# eagle.net
KiCad netlist of a schematic drawn in EAGLE
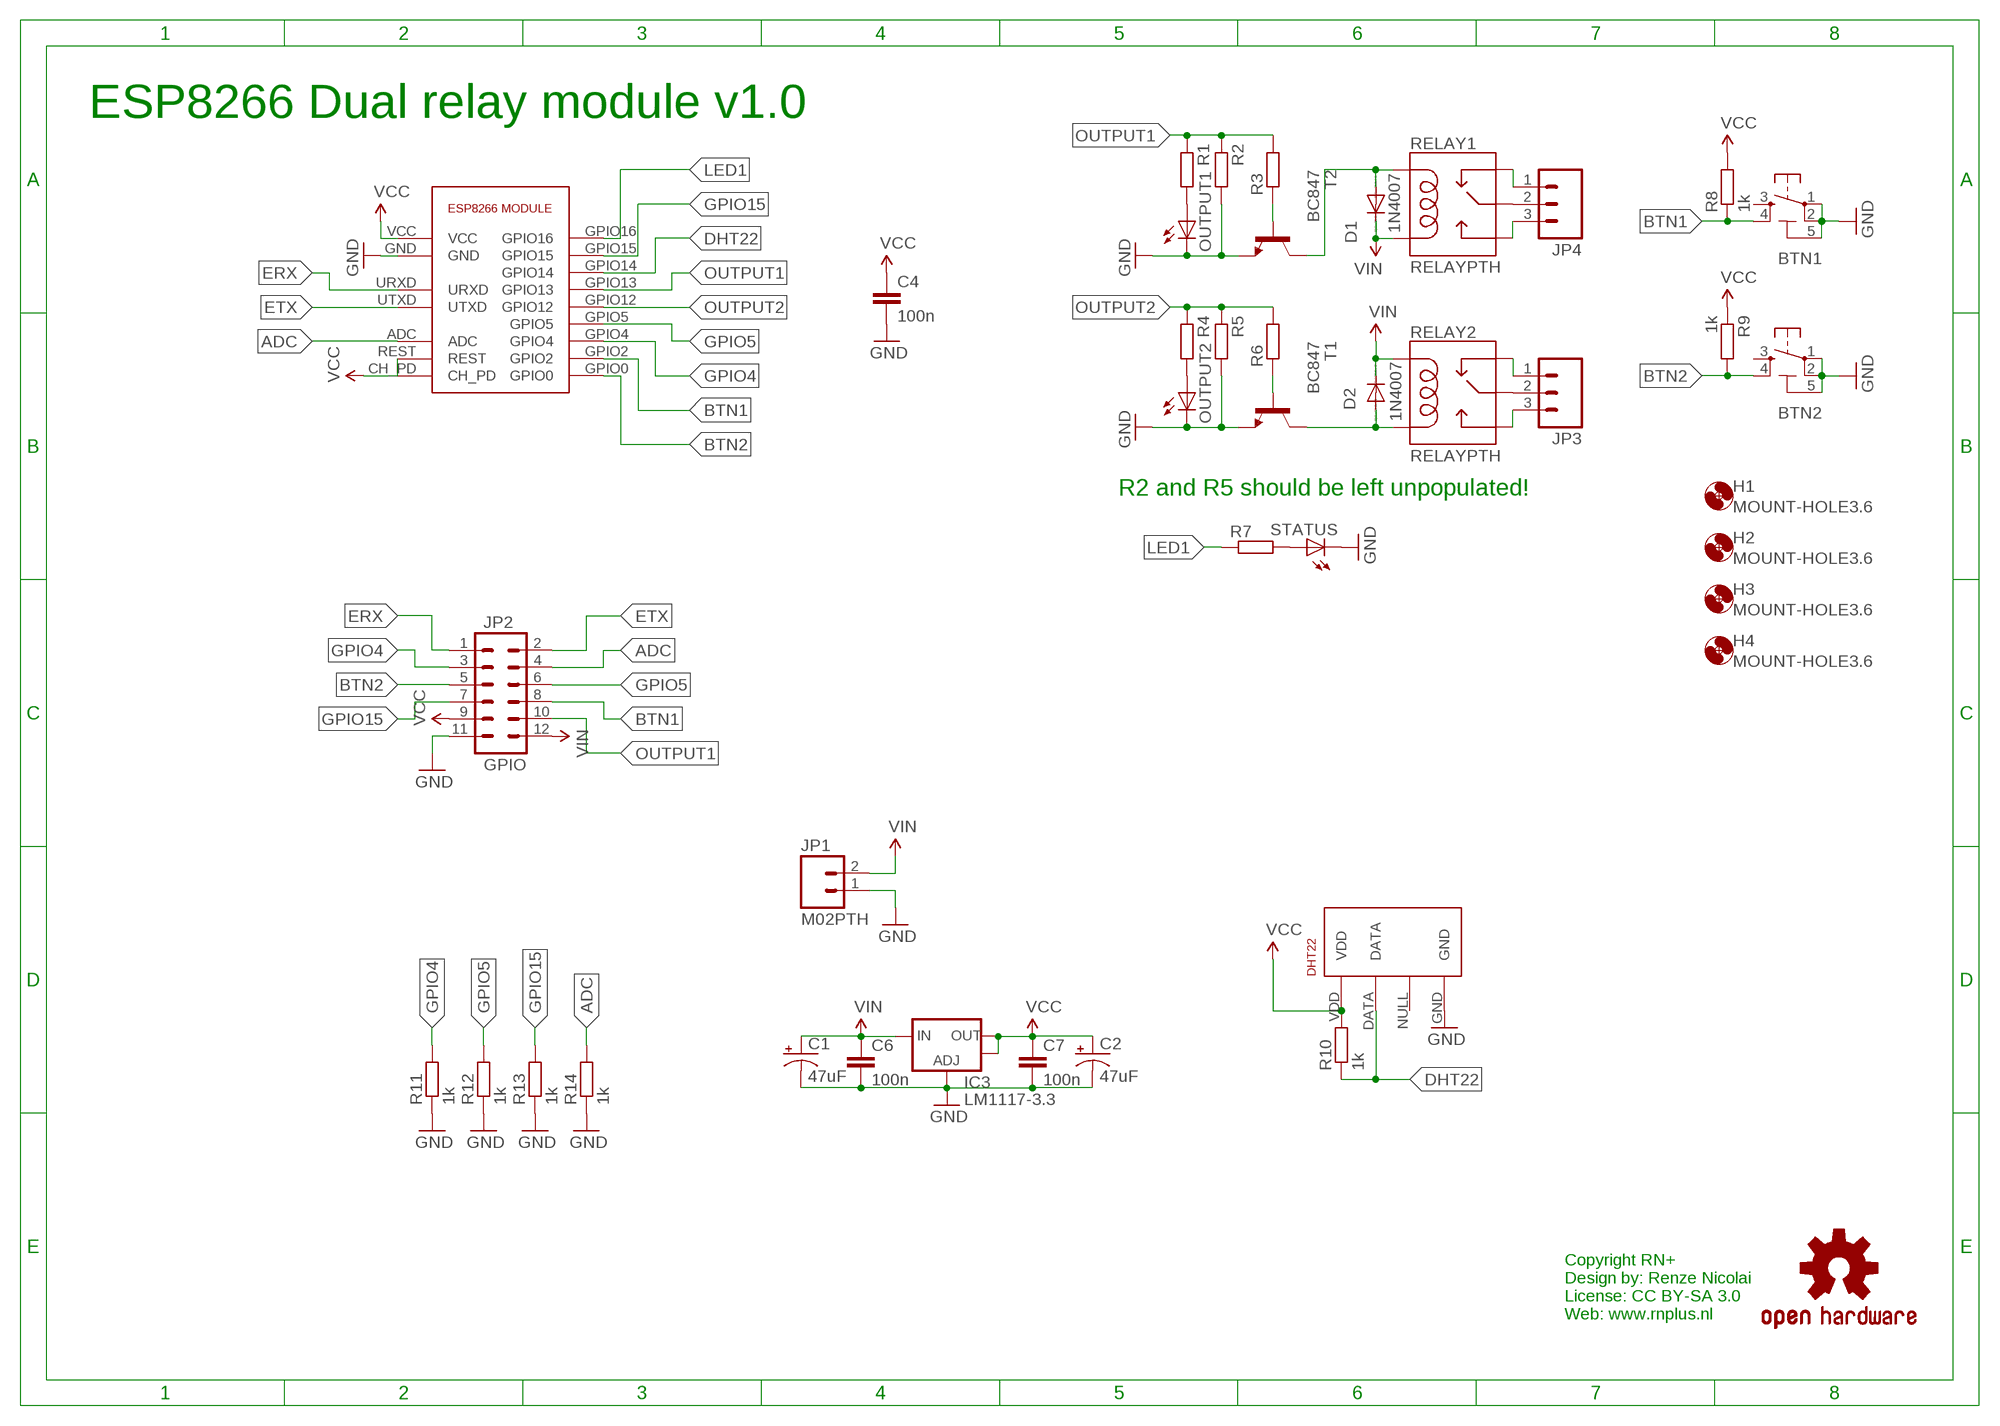
[diagram p0: schematic, sheet 1]

(export (version "E")
  (design (tool "Eeschema 10.0.6"))
  (components
    (comp (ref "BTN1")
      (value "SMARTPRJ_TS42")
      (footprint "eagle-import:SMARTPRJ_TS42")
      (libsource (lib "eagle-import") (part "SMARTPRJ_TS42"))
    )
    (comp (ref "BTN2")
      (value "SMARTPRJ_TS42")
      (footprint "eagle-import:SMARTPRJ_TS42")
      (libsource (lib "eagle-import") (part "SMARTPRJ_TS42"))
    )
    (comp (ref "C1")
      (value "47uF")
      (footprint "eagle-import:PANASONIC_D")
      (libsource (lib "eagle-import") (part "CAP_POLD"))
    )
    (comp (ref "C2")
      (value "47uF")
      (footprint "eagle-import:PANASONIC_D")
      (libsource (lib "eagle-import") (part "CAP_POLD"))
    )
    (comp (ref "C4")
      (value "100n")
      (footprint "eagle-import:C0805K")
      (libsource (lib "eagle-import") (part "C-EUC0805K"))
    )
    (comp (ref "C6")
      (value "100n")
      (footprint "eagle-import:C0805K")
      (libsource (lib "eagle-import") (part "C-EUC0805K"))
    )
    (comp (ref "C7")
      (value "100n")
      (footprint "eagle-import:C0805K")
      (libsource (lib "eagle-import") (part "C-EUC0805K"))
    )
    (comp (ref "D1")
      (value "1N4942")
      (footprint "eagle-import:DO41-10")
      (libsource (lib "eagle-import") (part "1N4942"))
    )
    (comp (ref "D2")
      (value "1N4942")
      (footprint "eagle-import:DO41-10")
      (libsource (lib "eagle-import") (part "1N4942"))
    )
    (comp (ref "DHT22")
      (value "RHT03_DHT-22_AM2302")
      (footprint "eagle-import:RHT03_DHT-22")
      (libsource (lib "eagle-import") (part "RHT03_DHT-22_AM2302"))
    )
    (comp (ref "ESP8266")
      (value "ESP8266ESP-07")
      (footprint "eagle-import:ESP-12")
      (libsource (lib "eagle-import") (part "ESP8266ESP-07"))
    )
    (comp (ref "H1")
      (value "MOUNT-HOLE3.6")
      (footprint "eagle-import:3,6")
      (libsource (lib "eagle-import") (part "MOUNT-HOLE3.6"))
    )
    (comp (ref "H2")
      (value "MOUNT-HOLE3.6")
      (footprint "eagle-import:3,6")
      (libsource (lib "eagle-import") (part "MOUNT-HOLE3.6"))
    )
    (comp (ref "H3")
      (value "MOUNT-HOLE3.6")
      (footprint "eagle-import:3,6")
      (libsource (lib "eagle-import") (part "MOUNT-HOLE3.6"))
    )
    (comp (ref "H4")
      (value "MOUNT-HOLE3.6")
      (footprint "eagle-import:3,6")
      (libsource (lib "eagle-import") (part "MOUNT-HOLE3.6"))
    )
    (comp (ref "IC3")
      (value "LM1117-3.3")
      (footprint "eagle-import:SOT223")
      (libsource (lib "eagle-import") (part "V_REG_LM1117SOT223"))
    )
    (comp (ref "JP1")
      (value "M02PTH")
      (footprint "eagle-import:1X02")
      (libsource (lib "eagle-import") (part "M02PTH"))
    )
    (comp (ref "JP2")
      (value "GPIO")
      (footprint "eagle-import:2X6")
      (libsource (lib "eagle-import") (part "M06X2PTH_FEMALE"))
    )
    (comp (ref "JP3")
      (value "M03-SCREW-5MM")
      (footprint "eagle-import:SCREWTERMINAL-5MM-3")
      (libsource (lib "eagle-import") (part "M03-SCREW-5MM"))
    )
    (comp (ref "JP4")
      (value "M03-SCREW-5MM")
      (footprint "eagle-import:SCREWTERMINAL-5MM-3")
      (libsource (lib "eagle-import") (part "M03-SCREW-5MM"))
    )
    (comp (ref "LOGO1")
      (value "OSHW-LOGOL")
      (footprint "eagle-import:OSHW-LOGO-L")
      (libsource (lib "eagle-import") (part "OSHW-LOGOL"))
    )
    (comp (ref "OUTPUT1")
      (value "LEDCHIP-LED0805")
      (footprint "eagle-import:CHIP-LED0805")
      (libsource (lib "eagle-import") (part "LEDCHIP-LED0805"))
    )
    (comp (ref "OUTPUT2")
      (value "LEDCHIP-LED0805")
      (footprint "eagle-import:CHIP-LED0805")
      (libsource (lib "eagle-import") (part "LEDCHIP-LED0805"))
    )
    (comp (ref "R1")
      (value "SMARTPRJ_R-EU_M0805")
      (footprint "eagle-import:SMARTPRJ_M0805")
      (libsource (lib "eagle-import") (part "SMARTPRJ_R-EU_M0805"))
    )
    (comp (ref "R2")
      (value "SMARTPRJ_R-EU_M0805")
      (footprint "eagle-import:SMARTPRJ_M0805")
      (libsource (lib "eagle-import") (part "SMARTPRJ_R-EU_M0805"))
    )
    (comp (ref "R3")
      (value "SMARTPRJ_R-EU_M0805")
      (footprint "eagle-import:SMARTPRJ_M0805")
      (libsource (lib "eagle-import") (part "SMARTPRJ_R-EU_M0805"))
    )
    (comp (ref "R4")
      (value "SMARTPRJ_R-EU_M0805")
      (footprint "eagle-import:SMARTPRJ_M0805")
      (libsource (lib "eagle-import") (part "SMARTPRJ_R-EU_M0805"))
    )
    (comp (ref "R5")
      (value "SMARTPRJ_R-EU_M0805")
      (footprint "eagle-import:SMARTPRJ_M0805")
      (libsource (lib "eagle-import") (part "SMARTPRJ_R-EU_M0805"))
    )
    (comp (ref "R6")
      (value "SMARTPRJ_R-EU_M0805")
      (footprint "eagle-import:SMARTPRJ_M0805")
      (libsource (lib "eagle-import") (part "SMARTPRJ_R-EU_M0805"))
    )
    (comp (ref "R7")
      (value "SMARTPRJ_R-EU_M0805")
      (footprint "eagle-import:SMARTPRJ_M0805")
      (libsource (lib "eagle-import") (part "SMARTPRJ_R-EU_M0805"))
    )
    (comp (ref "R8")
      (value "1k")
      (footprint "eagle-import:SMARTPRJ_M0805")
      (libsource (lib "eagle-import") (part "SMARTPRJ_R-EU_M0805"))
    )
    (comp (ref "R9")
      (value "1k")
      (footprint "eagle-import:SMARTPRJ_M0805")
      (libsource (lib "eagle-import") (part "SMARTPRJ_R-EU_M0805"))
    )
    (comp (ref "R10")
      (value "1k")
      (footprint "eagle-import:SMARTPRJ_M0805")
      (libsource (lib "eagle-import") (part "SMARTPRJ_R-EU_M0805"))
    )
    (comp (ref "R11")
      (value "1k")
      (footprint "eagle-import:SMARTPRJ_M0805")
      (libsource (lib "eagle-import") (part "SMARTPRJ_R-EU_M0805"))
    )
    (comp (ref "R12")
      (value "1k")
      (footprint "eagle-import:SMARTPRJ_M0805")
      (libsource (lib "eagle-import") (part "SMARTPRJ_R-EU_M0805"))
    )
    (comp (ref "R13")
      (value "1k")
      (footprint "eagle-import:SMARTPRJ_M0805")
      (libsource (lib "eagle-import") (part "SMARTPRJ_R-EU_M0805"))
    )
    (comp (ref "R14")
      (value "1k")
      (footprint "eagle-import:SMARTPRJ_M0805")
      (libsource (lib "eagle-import") (part "SMARTPRJ_R-EU_M0805"))
    )
    (comp (ref "RELAY1")
      (value "RELAYPTH")
      (footprint "eagle-import:SRD-05VDC-SL-C")
      (libsource (lib "eagle-import") (part "RELAYPTH"))
    )
    (comp (ref "RELAY2")
      (value "RELAYPTH")
      (footprint "eagle-import:SRD-05VDC-SL-C")
      (libsource (lib "eagle-import") (part "RELAYPTH"))
    )
    (comp (ref "STATUS")
      (value "LEDCHIP-LED0805")
      (footprint "eagle-import:CHIP-LED0805")
      (libsource (lib "eagle-import") (part "LEDCHIP-LED0805"))
    )
    (comp (ref "T1")
      (value "BC847")
      (footprint "eagle-import:SOT23")
      (libsource (lib "eagle-import") (part "BC847"))
    )
    (comp (ref "T2")
      (value "BC847")
      (footprint "eagle-import:SOT23")
      (libsource (lib "eagle-import") (part "BC847"))
    )
  )
  (nets
    (net (code "1") (name "ADC") (class "Default")
      (node (ref "ESP8266") (pin "ADC") (pinfunction "ADC_ADC") (pintype "bidirectional"))
      (node (ref "JP2") (pin "4") (pinfunction "4_4") (pintype "passive"))
      (node (ref "R14") (pin "2") (pinfunction "2_2") (pintype "passive"))
    )
    (net (code "2") (name "BTN1") (class "Default")
      (node (ref "BTN1") (pin "4") (pinfunction "4_4") (pintype "passive"))
      (node (ref "ESP8266") (pin "GPIO2") (pinfunction "GPIO2_GPIO2") (pintype "bidirectional"))
      (node (ref "JP2") (pin "8") (pinfunction "8_8") (pintype "passive"))
      (node (ref "R8") (pin "1") (pinfunction "1_1") (pintype "passive"))
    )
    (net (code "3") (name "BTN2") (class "Default")
      (node (ref "BTN2") (pin "4") (pinfunction "4_4") (pintype "passive"))
      (node (ref "ESP8266") (pin "GPIO0") (pinfunction "GPIO0_GPIO0") (pintype "bidirectional"))
      (node (ref "JP2") (pin "5") (pinfunction "5_5") (pintype "passive"))
      (node (ref "R9") (pin "2") (pinfunction "2_2") (pintype "passive"))
    )
    (net (code "4") (name "DHT22") (class "Default")
      (node (ref "DHT22") (pin "DATA") (pinfunction "DATA_DATA") (pintype "bidirectional"))
      (node (ref "ESP8266") (pin "GPIO14") (pinfunction "GPIO14_GPIO14") (pintype "bidirectional"))
      (node (ref "R10") (pin "1") (pinfunction "1_1") (pintype "passive"))
    )
    (net (code "5") (name "ERX") (class "Default")
      (node (ref "ESP8266") (pin "URXD") (pinfunction "URXD_URXD") (pintype "input"))
      (node (ref "JP2") (pin "1") (pinfunction "1_1") (pintype "passive"))
    )
    (net (code "6") (name "ETX") (class "Default")
      (node (ref "ESP8266") (pin "UTXD") (pinfunction "UTXD_UTXD") (pintype "output"))
      (node (ref "JP2") (pin "2") (pinfunction "2_2") (pintype "passive"))
    )
    (net (code "7") (name "GND") (class "Default")
      (node (ref "BTN1") (pin "1") (pinfunction "1_1") (pintype "passive"))
      (node (ref "BTN1") (pin "2") (pinfunction "2_2") (pintype "passive"))
      (node (ref "BTN1") (pin "5") (pinfunction "5-GND_5") (pintype "power_in"))
      (node (ref "BTN2") (pin "1") (pinfunction "1_1") (pintype "passive"))
      (node (ref "BTN2") (pin "2") (pinfunction "2_2") (pintype "passive"))
      (node (ref "BTN2") (pin "5") (pinfunction "5-GND_5") (pintype "power_in"))
      (node (ref "C1") (pin "-") (pinfunction "-_-") (pintype "passive"))
      (node (ref "C2") (pin "-") (pinfunction "-_-") (pintype "passive"))
      (node (ref "C4") (pin "2") (pinfunction "2_2") (pintype "passive"))
      (node (ref "C6") (pin "2") (pinfunction "2_2") (pintype "passive"))
      (node (ref "C7") (pin "2") (pinfunction "2_2") (pintype "passive"))
      (node (ref "DHT22") (pin "GND") (pinfunction "GND_GND") (pintype "power_in"))
      (node (ref "ESP8266") (pin "GND") (pinfunction "GND_GND") (pintype "power_in"))
      (node (ref "IC3") (pin "1") (pinfunction "ADJ_1") (pintype "input"))
      (node (ref "JP1") (pin "1") (pinfunction "1_1") (pintype "passive"))
      (node (ref "JP2") (pin "11") (pinfunction "11_11") (pintype "passive"))
      (node (ref "OUTPUT1") (pin "C") (pinfunction "C_C") (pintype "passive"))
      (node (ref "OUTPUT2") (pin "C") (pinfunction "C_C") (pintype "passive"))
      (node (ref "R11") (pin "1") (pinfunction "1_1") (pintype "passive"))
      (node (ref "R12") (pin "1") (pinfunction "1_1") (pintype "passive"))
      (node (ref "R13") (pin "1") (pinfunction "1_1") (pintype "passive"))
      (node (ref "R14") (pin "1") (pinfunction "1_1") (pintype "passive"))
      (node (ref "R2") (pin "2") (pinfunction "2_2") (pintype "passive"))
      (node (ref "R5") (pin "2") (pinfunction "2_2") (pintype "passive"))
      (node (ref "STATUS") (pin "C") (pinfunction "C_C") (pintype "passive"))
      (node (ref "T1") (pin "2") (pinfunction "E_2") (pintype "passive"))
      (node (ref "T2") (pin "2") (pinfunction "E_2") (pintype "passive"))
    )
    (net (code "8") (name "GPIO4") (class "Default")
      (node (ref "ESP8266") (pin "GPIO4") (pinfunction "GPIO4_GPIO4") (pintype "bidirectional"))
      (node (ref "JP2") (pin "3") (pinfunction "3_3") (pintype "passive"))
      (node (ref "R11") (pin "2") (pinfunction "2_2") (pintype "passive"))
    )
    (net (code "9") (name "GPIO5") (class "Default")
      (node (ref "ESP8266") (pin "GPIO5") (pinfunction "GPIO5_GPIO5") (pintype "bidirectional"))
      (node (ref "JP2") (pin "6") (pinfunction "6_6") (pintype "passive"))
      (node (ref "R12") (pin "2") (pinfunction "2_2") (pintype "passive"))
    )
    (net (code "10") (name "GPIO15") (class "Default")
      (node (ref "ESP8266") (pin "GPIO15") (pinfunction "GPIO15_GPIO15") (pintype "bidirectional"))
      (node (ref "JP2") (pin "7") (pinfunction "7_7") (pintype "passive"))
      (node (ref "R13") (pin "2") (pinfunction "2_2") (pintype "passive"))
    )
    (net (code "11") (name "LED1") (class "Default")
      (node (ref "ESP8266") (pin "GPIO16") (pinfunction "GPIO16_GPIO16") (pintype "bidirectional"))
      (node (ref "R7") (pin "1") (pinfunction "1_1") (pintype "passive"))
    )
    (net (code "12") (name "Net-(JP3-Pad2)") (class "Default")
      (node (ref "JP3") (pin "2") (pinfunction "2_2") (pintype "passive"))
      (node (ref "RELAY2") (pin "SWCOMMON") (pinfunction "SWCOMMON_SWCOMMON") (pintype "bidirectional"))
    )
    (net (code "13") (name "Net-(JP3-Pad3)") (class "Default")
      (node (ref "JP3") (pin "3") (pinfunction "3_3") (pintype "passive"))
      (node (ref "RELAY2") (pin "SWOPEN") (pinfunction "SWOPEN_SWOPEN") (pintype "bidirectional"))
    )
    (net (code "14") (name "Net-(JP4-Pad2)") (class "Default")
      (node (ref "JP4") (pin "2") (pinfunction "2_2") (pintype "passive"))
      (node (ref "RELAY1") (pin "SWCOMMON") (pinfunction "SWCOMMON_SWCOMMON") (pintype "bidirectional"))
    )
    (net (code "15") (name "Net-(JP4-Pad3)") (class "Default")
      (node (ref "JP4") (pin "3") (pinfunction "3_3") (pintype "passive"))
      (node (ref "RELAY1") (pin "SWOPEN") (pinfunction "SWOPEN_SWOPEN") (pintype "bidirectional"))
    )
    (net (code "16") (name "Net-(OUTPUT1-PadA)") (class "Default")
      (node (ref "OUTPUT1") (pin "A") (pinfunction "A_A") (pintype "passive"))
      (node (ref "R1") (pin "2") (pinfunction "2_2") (pintype "passive"))
    )
    (net (code "17") (name "Net-(OUTPUT2-PadA)") (class "Default")
      (node (ref "OUTPUT2") (pin "A") (pinfunction "A_A") (pintype "passive"))
      (node (ref "R4") (pin "2") (pinfunction "2_2") (pintype "passive"))
    )
    (net (code "18") (name "Net-(R7-Pad2)") (class "Default")
      (node (ref "R7") (pin "2") (pinfunction "2_2") (pintype "passive"))
      (node (ref "STATUS") (pin "A") (pinfunction "A_A") (pintype "passive"))
    )
    (net (code "19") (name "Net-(RELAY1-SWCLOSE)") (class "Default")
      (node (ref "JP4") (pin "1") (pinfunction "1_1") (pintype "passive"))
      (node (ref "RELAY1") (pin "SWCLOSED") (pinfunction "SWCLOSE_SWCLOSED") (pintype "bidirectional"))
    )
    (net (code "20") (name "Net-(RELAY2-SWCLOSE)") (class "Default")
      (node (ref "JP3") (pin "1") (pinfunction "1_1") (pintype "passive"))
      (node (ref "RELAY2") (pin "SWCLOSED") (pinfunction "SWCLOSE_SWCLOSED") (pintype "bidirectional"))
    )
    (net (code "21") (name "Net-(T1-B)") (class "Default")
      (node (ref "R6") (pin "1") (pinfunction "1_1") (pintype "passive"))
      (node (ref "T1") (pin "1") (pinfunction "B_1") (pintype "passive"))
    )
    (net (code "22") (name "Net-(T1-C)") (class "Default")
      (node (ref "D2") (pin "A") (pinfunction "A_A") (pintype "passive"))
      (node (ref "RELAY2") (pin "COIL0") (pinfunction "COIL0_COIL0") (pintype "bidirectional"))
      (node (ref "T1") (pin "3") (pinfunction "C_3") (pintype "passive"))
    )
    (net (code "23") (name "Net-(T2-B)") (class "Default")
      (node (ref "R3") (pin "1") (pinfunction "1_1") (pintype "passive"))
      (node (ref "T2") (pin "1") (pinfunction "B_1") (pintype "passive"))
    )
    (net (code "24") (name "Net-(T2-C)") (class "Default")
      (node (ref "D1") (pin "A") (pinfunction "A_A") (pintype "passive"))
      (node (ref "RELAY1") (pin "COIL1") (pinfunction "COIL1_COIL1") (pintype "bidirectional"))
      (node (ref "T2") (pin "3") (pinfunction "C_3") (pintype "passive"))
    )
    (net (code "25") (name "OUTPUT1") (class "Default")
      (node (ref "ESP8266") (pin "GPIO13") (pinfunction "GPIO13_GPIO13") (pintype "bidirectional"))
      (node (ref "JP2") (pin "10") (pinfunction "10_10") (pintype "passive"))
      (node (ref "R1") (pin "1") (pinfunction "1_1") (pintype "passive"))
      (node (ref "R2") (pin "1") (pinfunction "1_1") (pintype "passive"))
      (node (ref "R3") (pin "2") (pinfunction "2_2") (pintype "passive"))
    )
    (net (code "26") (name "OUTPUT2") (class "Default")
      (node (ref "ESP8266") (pin "GPIO12") (pinfunction "GPIO12_GPIO12") (pintype "bidirectional"))
      (node (ref "R4") (pin "1") (pinfunction "1_1") (pintype "passive"))
      (node (ref "R5") (pin "1") (pinfunction "1_1") (pintype "passive"))
      (node (ref "R6") (pin "2") (pinfunction "2_2") (pintype "passive"))
    )
    (net (code "27") (name "VCC") (class "Default")
      (node (ref "C2") (pin "+") (pinfunction "+_+") (pintype "passive"))
      (node (ref "C4") (pin "1") (pinfunction "1_1") (pintype "passive"))
      (node (ref "C7") (pin "1") (pinfunction "1_1") (pintype "passive"))
      (node (ref "DHT22") (pin "VDD") (pinfunction "VDD_VDD") (pintype "power_in"))
      (node (ref "ESP8266") (pin "CH_PD") (pinfunction "CH_PD_CH_PD") (pintype "bidirectional"))
      (node (ref "ESP8266") (pin "REST") (pinfunction "REST_REST") (pintype "bidirectional"))
      (node (ref "ESP8266") (pin "VCC") (pinfunction "VCC_VCC") (pintype "power_in"))
      (node (ref "IC3") (pin "2") (pinfunction "OUT_2") (pintype "output"))
      (node (ref "IC3") (pin "4") (pinfunction "OUT_4") (pintype "output"))
      (node (ref "JP2") (pin "9") (pinfunction "9_9") (pintype "passive"))
      (node (ref "R10") (pin "2") (pinfunction "2_2") (pintype "passive"))
      (node (ref "R8") (pin "2") (pinfunction "2_2") (pintype "passive"))
      (node (ref "R9") (pin "1") (pinfunction "1_1") (pintype "passive"))
    )
    (net (code "28") (name "VIN") (class "Default")
      (node (ref "C1") (pin "+") (pinfunction "+_+") (pintype "passive"))
      (node (ref "C6") (pin "1") (pinfunction "1_1") (pintype "passive"))
      (node (ref "D1") (pin "C") (pinfunction "C_C") (pintype "passive"))
      (node (ref "D2") (pin "C") (pinfunction "C_C") (pintype "passive"))
      (node (ref "IC3") (pin "3") (pinfunction "IN_3") (pintype "input"))
      (node (ref "JP1") (pin "2") (pinfunction "2_2") (pintype "passive"))
      (node (ref "JP2") (pin "12") (pinfunction "12_12") (pintype "passive"))
      (node (ref "RELAY1") (pin "COIL0") (pinfunction "COIL0_COIL0") (pintype "bidirectional"))
      (node (ref "RELAY2") (pin "COIL1") (pinfunction "COIL1_COIL1") (pintype "bidirectional"))
    )
    (net (code "29") (name "unconnected-(BTN1-Pad3)") (class "Default")
      (node (ref "BTN1") (pin "3") (pinfunction "3_3") (pintype "passive"))
    )
    (net (code "30") (name "unconnected-(BTN2-Pad3)") (class "Default")
      (node (ref "BTN2") (pin "3") (pinfunction "3_3") (pintype "passive"))
    )
    (net (code "31") (name "unconnected-(DHT22-PadNULL)") (class "Default")
      (node (ref "DHT22") (pin "NULL") (pinfunction "NULL_NULL") (pintype "no_connect"))
    )
  )
)
